# Adafruit_ADXL345.net
KiCad netlist of a schematic drawn in EAGLE
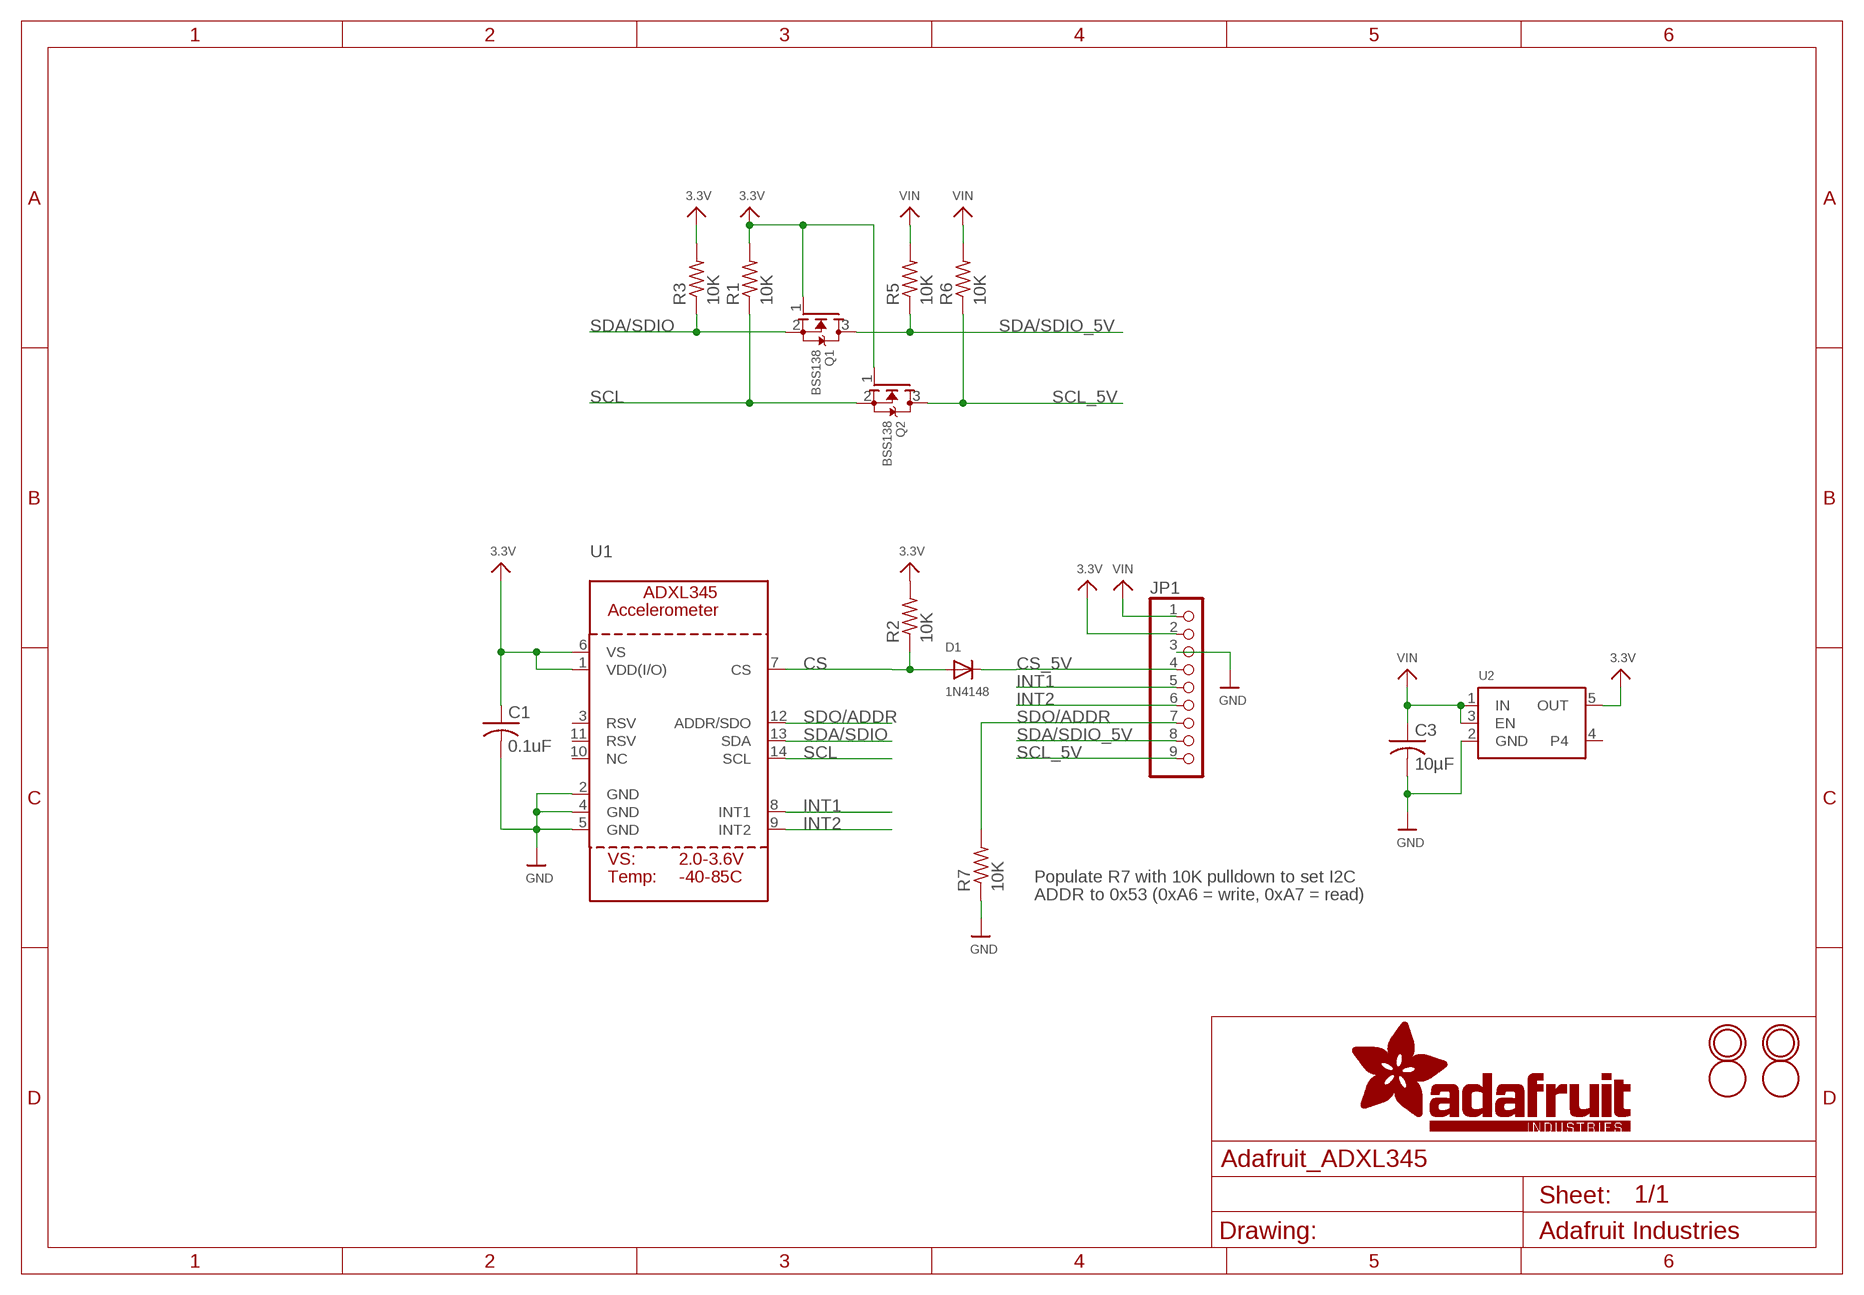
[diagram p0: schematic, sheet 1]

(export (version "E")
  (design (tool "Eeschema 10.0.6"))
  (components
    (comp (ref "C1")
      (value "0.1uF")
      (footprint "eagle-import:C0805")
      (libsource (lib "eagle-import") (part "C-USC0805"))
    )
    (comp (ref "C3")
      (value "10µF")
      (footprint "eagle-import:C0805")
      (libsource (lib "eagle-import") (part "C-USC0805"))
    )
    (comp (ref "D1")
      (value "1N4148")
      (footprint "eagle-import:SOD-323")
      (libsource (lib "eagle-import") (part "DIODESOD-323"))
    )
    (comp (ref "JP1")
      (value "HEADER-1X970MIL")
      (footprint "eagle-import:1X09_ROUND_70")
      (libsource (lib "eagle-import") (part "HEADER-1X970MIL"))
    )
    (comp (ref "Q1")
      (value "BSS138")
      (footprint "eagle-import:SOT23-WIDE")
      (libsource (lib "eagle-import") (part "MOSFET-NWIDE"))
    )
    (comp (ref "Q2")
      (value "BSS138")
      (footprint "eagle-import:SOT23-WIDE")
      (libsource (lib "eagle-import") (part "MOSFET-NWIDE"))
    )
    (comp (ref "R1")
      (value "10K")
      (footprint "eagle-import:R0805")
      (libsource (lib "eagle-import") (part "R-US_R0805"))
    )
    (comp (ref "R2")
      (value "10K")
      (footprint "eagle-import:R0805")
      (libsource (lib "eagle-import") (part "R-US_R0805"))
    )
    (comp (ref "R3")
      (value "10K")
      (footprint "eagle-import:R0805")
      (libsource (lib "eagle-import") (part "R-US_R0805"))
    )
    (comp (ref "R5")
      (value "10K")
      (footprint "eagle-import:R0805")
      (libsource (lib "eagle-import") (part "R-US_R0805"))
    )
    (comp (ref "R6")
      (value "10K")
      (footprint "eagle-import:R0805")
      (libsource (lib "eagle-import") (part "R-US_R0805"))
    )
    (comp (ref "R7")
      (value "10K")
      (footprint "eagle-import:R0805")
      (libsource (lib "eagle-import") (part "R-US_R0805"))
    )
    (comp (ref "U$1")
      (value "FIDUCIAL")
      (footprint "eagle-import:FIDUCIAL_1MM")
      (libsource (lib "eagle-import") (part "FIDUCIAL"))
    )
    (comp (ref "U$3")
      (value "FIDUCIAL")
      (footprint "eagle-import:FIDUCIAL_1MM")
      (libsource (lib "eagle-import") (part "FIDUCIAL"))
    )
    (comp (ref "U$4")
      (value "MOUNTINGHOLE2.5")
      (footprint "eagle-import:MOUNTINGHOLE_2.5_PLATED")
      (libsource (lib "eagle-import") (part "MOUNTINGHOLE2.5"))
    )
    (comp (ref "U$6")
      (value "MOUNTINGHOLE2.5")
      (footprint "eagle-import:MOUNTINGHOLE_2.5_PLATED")
      (libsource (lib "eagle-import") (part "MOUNTINGHOLE2.5"))
    )
    (comp (ref "U1")
      (value "ACCEL_ADXL345")
      (footprint "eagle-import:LGA14")
      (libsource (lib "eagle-import") (part "ACCEL_ADXL345"))
    )
    (comp (ref "U2")
      (value "VREG_SOT23-5")
      (footprint "eagle-import:SOT23-5")
      (libsource (lib "eagle-import") (part "VREG_SOT23-5"))
    )
  )
  (nets
    (net (code "1") (name "/CS") (class "Default")
      (node (ref "D1") (pin "A") (pinfunction "A_A") (pintype "passive"))
      (node (ref "R2") (pin "1") (pinfunction "1_1") (pintype "passive"))
      (node (ref "U1") (pin "7") (pinfunction "CS_7") (pintype "bidirectional"))
    )
    (net (code "2") (name "/CS_5V") (class "Default")
      (node (ref "D1") (pin "C") (pinfunction "C_C") (pintype "passive"))
      (node (ref "JP1") (pin "4") (pinfunction "4_4") (pintype "passive"))
    )
    (net (code "3") (name "/INT1") (class "Default")
      (node (ref "JP1") (pin "5") (pinfunction "5_5") (pintype "passive"))
      (node (ref "U1") (pin "8") (pinfunction "INT1_8") (pintype "bidirectional"))
    )
    (net (code "4") (name "/INT2") (class "Default")
      (node (ref "JP1") (pin "6") (pinfunction "6_6") (pintype "passive"))
      (node (ref "U1") (pin "9") (pinfunction "INT2_9") (pintype "bidirectional"))
    )
    (net (code "5") (name "/SCL") (class "Default")
      (node (ref "Q2") (pin "2") (pinfunction "S_2") (pintype "bidirectional"))
      (node (ref "R1") (pin "1") (pinfunction "1_1") (pintype "passive"))
      (node (ref "U1") (pin "14") (pinfunction "SCL_14") (pintype "bidirectional"))
    )
    (net (code "6") (name "/SCL_5V") (class "Default")
      (node (ref "JP1") (pin "9") (pinfunction "9_9") (pintype "passive"))
      (node (ref "Q2") (pin "3") (pinfunction "D_3") (pintype "bidirectional"))
      (node (ref "R6") (pin "1") (pinfunction "1_1") (pintype "passive"))
    )
    (net (code "7") (name "/SDA{slash}SDIO") (class "Default")
      (node (ref "Q1") (pin "2") (pinfunction "S_2") (pintype "bidirectional"))
      (node (ref "R3") (pin "1") (pinfunction "1_1") (pintype "passive"))
      (node (ref "U1") (pin "13") (pinfunction "SDA_13") (pintype "bidirectional"))
    )
    (net (code "8") (name "/SDA{slash}SDIO_5V") (class "Default")
      (node (ref "JP1") (pin "8") (pinfunction "8_8") (pintype "passive"))
      (node (ref "Q1") (pin "3") (pinfunction "D_3") (pintype "bidirectional"))
      (node (ref "R5") (pin "1") (pinfunction "1_1") (pintype "passive"))
    )
    (net (code "9") (name "/SDO{slash}ADDR") (class "Default")
      (node (ref "JP1") (pin "7") (pinfunction "7_7") (pintype "passive"))
      (node (ref "R7") (pin "2") (pinfunction "2_2") (pintype "passive"))
      (node (ref "U1") (pin "12") (pinfunction "ADDR/SDO_12") (pintype "bidirectional"))
    )
    (net (code "10") (name "3.3V") (class "Default")
      (node (ref "C1") (pin "1") (pinfunction "1_1") (pintype "passive"))
      (node (ref "JP1") (pin "2") (pinfunction "2_2") (pintype "passive"))
      (node (ref "Q1") (pin "1") (pinfunction "G_1") (pintype "bidirectional"))
      (node (ref "Q2") (pin "1") (pinfunction "G_1") (pintype "bidirectional"))
      (node (ref "R1") (pin "2") (pinfunction "2_2") (pintype "passive"))
      (node (ref "R2") (pin "2") (pinfunction "2_2") (pintype "passive"))
      (node (ref "R3") (pin "2") (pinfunction "2_2") (pintype "passive"))
      (node (ref "U1") (pin "1") (pinfunction "VDD(I/O)_1") (pintype "bidirectional"))
      (node (ref "U1") (pin "6") (pinfunction "VS_6") (pintype "bidirectional"))
      (node (ref "U2") (pin "5") (pinfunction "OUT_5") (pintype "bidirectional"))
    )
    (net (code "11") (name "GND") (class "Default")
      (node (ref "C1") (pin "2") (pinfunction "2_2") (pintype "passive"))
      (node (ref "C3") (pin "2") (pinfunction "2_2") (pintype "passive"))
      (node (ref "JP1") (pin "3") (pinfunction "3_3") (pintype "passive"))
      (node (ref "R7") (pin "1") (pinfunction "1_1") (pintype "passive"))
      (node (ref "U1") (pin "2") (pinfunction "GND_2") (pintype "bidirectional"))
      (node (ref "U1") (pin "4") (pinfunction "GND_4") (pintype "bidirectional"))
      (node (ref "U1") (pin "5") (pinfunction "GND_5") (pintype "bidirectional"))
      (node (ref "U2") (pin "2") (pinfunction "GND_2") (pintype "bidirectional"))
    )
    (net (code "12") (name "VIN") (class "Default")
      (node (ref "C3") (pin "1") (pinfunction "1_1") (pintype "passive"))
      (node (ref "JP1") (pin "1") (pinfunction "1_1") (pintype "passive"))
      (node (ref "R5") (pin "2") (pinfunction "2_2") (pintype "passive"))
      (node (ref "R6") (pin "2") (pinfunction "2_2") (pintype "passive"))
      (node (ref "U2") (pin "1") (pinfunction "IN_1") (pintype "bidirectional"))
      (node (ref "U2") (pin "3") (pinfunction "EN_3") (pintype "bidirectional"))
    )
    (net (code "13") (name "unconnected-(U1-NC-Pad10)") (class "Default")
      (node (ref "U1") (pin "10") (pinfunction "NC_10") (pintype "bidirectional"))
    )
    (net (code "14") (name "unconnected-(U1-RSV-Pad3)") (class "Default")
      (node (ref "U1") (pin "3") (pinfunction "RSV_3") (pintype "bidirectional"))
    )
    (net (code "15") (name "unconnected-(U1-RSV-Pad11)") (class "Default")
      (node (ref "U1") (pin "11") (pinfunction "RSV_11") (pintype "bidirectional"))
    )
    (net (code "16") (name "unconnected-(U2-P4-Pad4)") (class "Default")
      (node (ref "U2") (pin "4") (pinfunction "P4_4") (pintype "bidirectional"))
    )
  )
)
